# HashPower2.net
KiCad netlist of a schematic drawn in Altium Designer
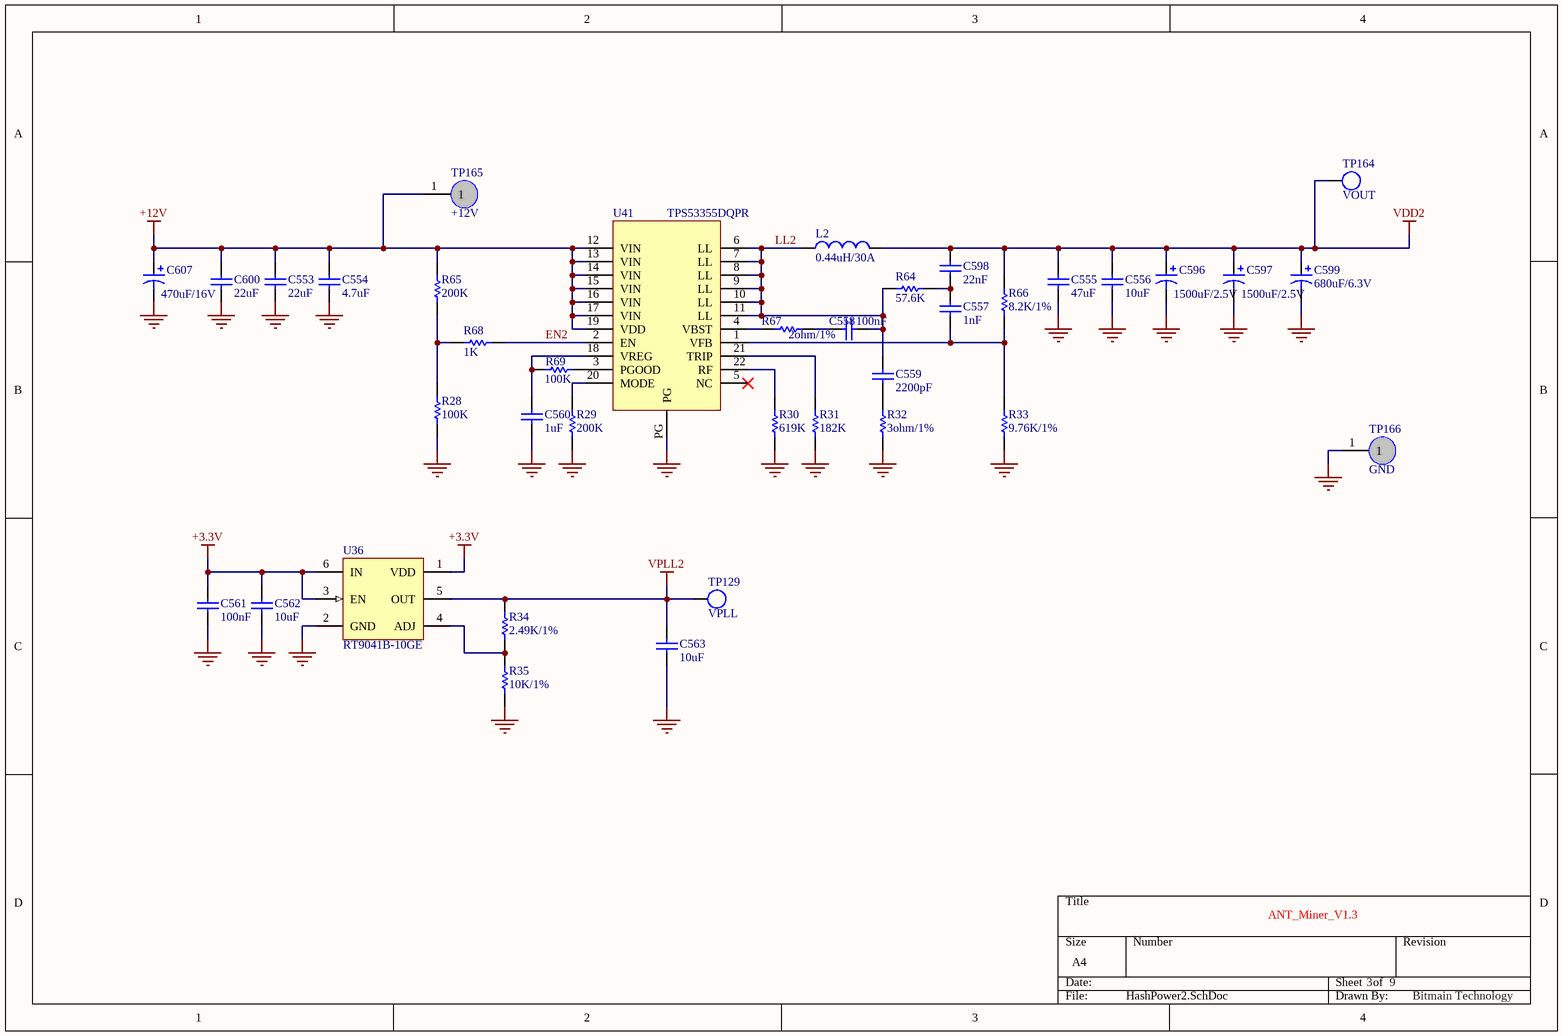
[diagram p0: HashPower2.SchDoc]

(export (version "E")
  (design (tool "Eeschema 10.0.6"))
  (components
    (comp (ref "C553")
      (value "22uF")
      (footprint "CC1210(3225)")
      (description "Capacitor")
      (libsource (lib "ANT_Miner_V1.3") (part "Cap"))
    )
    (comp (ref "C554")
      (value "4.7uF")
      (footprint "CC0805(2012)")
      (description "Capacitor")
      (libsource (lib "ANT_Miner_V1.3") (part "Cap"))
    )
    (comp (ref "C555")
      (value "47uF")
      (footprint "CAPC3225L")
      (description "Capacitor (Semiconductor SIM Model)")
      (fields (field (name "PUBLISHER") "Altium Limited"))
      (libsource (lib "Miscellaneous Devices") (part "Cap Semi"))
    )
    (comp (ref "C556")
      (value "10uF")
      (footprint "CAPC2012L")
      (description "Capacitor (Semiconductor SIM Model)")
      (fields (field (name "PUBLISHER") "Altium Limited"))
      (libsource (lib "Miscellaneous Devices") (part "Cap Semi"))
    )
    (comp (ref "C557")
      (value "1nF")
      (footprint "CC0603(1608)")
      (description "Capacitor")
      (libsource (lib "ANT_Miner_V1.3") (part "Cap"))
    )
    (comp (ref "C558")
      (value "100nF")
      (footprint "CC0603(1608)")
      (description "Capacitor")
      (libsource (lib "ANT_Miner_V1.3") (part "Cap"))
    )
    (comp (ref "C559")
      (value "2200pF")
      (footprint "CC0603(1608)")
      (description "Capacitor")
      (libsource (lib "ANT_Miner_V1.3") (part "Cap"))
    )
    (comp (ref "C560")
      (value "1uF")
      (footprint "CC0603(1608)")
      (description "Capacitor")
      (libsource (lib "ANT_Miner_V1.3") (part "Cap"))
    )
    (comp (ref "C561")
      (value "100nF")
      (footprint "CC0603(1608)")
      (description "Capacitor (Semiconductor SIM Model)")
      (fields (field (name "PUBLISHER") "Altium Limited"))
      (libsource (lib "CtrlUnit_10U_V1.0") (part "Cap Semi"))
    )
    (comp (ref "C562")
      (value "10uF")
      (footprint "CC0805(2012)")
      (description "Capacitor (Semiconductor SIM Model)")
      (fields (field (name "PUBLISHER") "Altium Limited"))
      (libsource (lib "CtrlUnit_10U_V1.0") (part "Cap Semi"))
    )
    (comp (ref "C563")
      (value "10uF")
      (footprint "CC0805(2012)")
      (description "Capacitor (Semiconductor SIM Model)")
      (fields (field (name "PUBLISHER") "Altium Limited"))
      (libsource (lib "CtrlUnit_10U_V1.0") (part "Cap Semi"))
    )
    (comp (ref "C596")
      (value "1500uF/2.5V")
      (footprint "F12")
      (description "Polarized Capacitor (SMD)")
      (fields (field (name "Comment") "1500uF/4V"))
      (libsource (lib "ANT_Miner_V1.3") (part "Cap Pol2"))
    )
    (comp (ref "C597")
      (value "1500uF/2.5V")
      (footprint "F12")
      (description "Polarized Capacitor (SMD)")
      (fields (field (name "Comment") "1500uF/4V"))
      (libsource (lib "ANT_Miner_V1.3") (part "Cap Pol2"))
    )
    (comp (ref "C598")
      (value "22nF")
      (footprint "CC0603(1608)")
      (description "Capacitor")
      (libsource (lib "ANT_Miner_V1.3") (part "Cap"))
    )
    (comp (ref "C599")
      (value "680uF/6.3V")
      (footprint "D")
      (description "Polarized Capacitor (Surface Mount)")
      (fields (field (name "PUBLISHER") "Altium Limited"))
      (libsource (lib "Miscellaneous Devices") (part "Cap Pol3"))
    )
    (comp (ref "C600")
      (value "22uF")
      (footprint "CC1210(3225)")
      (description "Capacitor")
      (libsource (lib "ANT_Miner_V1.3") (part "Cap"))
    )
    (comp (ref "C607")
      (value "470uF/16V")
      (footprint "E12")
      (description "Polarized Capacitor (SMD)")
      (libsource (lib "ANT_Miner_V1.3") (part "Cap Pol2"))
    )
    (comp (ref "L2")
      (value "0.44uH/30A")
      (footprint "IHLP5050")
      (description "Inductor")
      (fields (field (name "PUBLISHER") "Altium Limited"))
      (libsource (lib "Miscellaneous Devices") (part "Inductor"))
    )
    (comp (ref "R28")
      (value "100K")
      (footprint "RR0603(1608)")
      (description "Resistor")
      (libsource (lib "ANT_Miner_V1.3") (part "Res1"))
    )
    (comp (ref "R29")
      (value "200K")
      (footprint "RR0603(1608)")
      (description "Resistor")
      (libsource (lib "ANT_Miner_V1.3") (part "Res1"))
    )
    (comp (ref "R30")
      (value "619K")
      (footprint "RR0603(1608)")
      (description "Resistor")
      (libsource (lib "ANT_Miner_V1.3") (part "Res1"))
    )
    (comp (ref "R31")
      (value "182K")
      (footprint "RR0603(1608)")
      (description "Resistor")
      (libsource (lib "ANT_Miner_V1.3") (part "Res1"))
    )
    (comp (ref "R32")
      (value "3ohm/1%")
      (footprint "RR0603(1608)")
      (description "Resistor")
      (fields (field (name "Comment") "3"))
      (libsource (lib "ANT_Miner_V1.3") (part "Res1"))
    )
    (comp (ref "R33")
      (value "9.76K/1%")
      (footprint "RR0603(1608)")
      (description "Resistor")
      (libsource (lib "ANT_Miner_V1.3") (part "Res1"))
    )
    (comp (ref "R34")
      (value "2.49K/1%")
      (footprint "RR0603(1608)")
      (description "Resistor")
      (fields (field (name "PUBLISHER") "Altium Limited"))
      (libsource (lib "CtrlUnit_10U_V1.0") (part "Res1"))
    )
    (comp (ref "R35")
      (value "10K/1%")
      (footprint "RR0603(1608)")
      (description "Resistor")
      (fields (field (name "PUBLISHER") "Altium Limited"))
      (libsource (lib "CtrlUnit_10U_V1.0") (part "Res1"))
    )
    (comp (ref "R64")
      (value "57.6K")
      (footprint "RR0603(1608)")
      (description "Resistor")
      (libsource (lib "ANT_Miner_V1.3") (part "Res1"))
    )
    (comp (ref "R65")
      (value "200K")
      (footprint "RR0603(1608)")
      (description "Resistor")
      (libsource (lib "ANT_Miner_V1.3") (part "Res1"))
    )
    (comp (ref "R66")
      (value "8.2K/1%")
      (footprint "RR0603(1608)")
      (description "Resistor")
      (libsource (lib "ANT_Miner_V1.3") (part "Res1"))
    )
    (comp (ref "R67")
      (value "2ohm/1%")
      (footprint "RR0603(1608)")
      (description "Resistor")
      (fields (field (name "Comment") "2"))
      (libsource (lib "ANT_Miner_V1.3") (part "Res1"))
    )
    (comp (ref "R68")
      (value "1K")
      (footprint "RR0603(1608)")
      (description "Resistor")
      (libsource (lib "ANT_Miner_V1.3") (part "Res1"))
    )
    (comp (ref "R69")
      (value "100K")
      (footprint "RR0603(1608)")
      (description "Resistor")
      (libsource (lib "ANT_Miner_V1.3") (part "Res1"))
    )
    (comp (ref "TP129")
      (value "VPLL")
      (footprint "TP_SMD_1.0")
      (description "Test Point")
      (libsource (lib "BitMain_Miner_1") (part "TP"))
    )
    (comp (ref "TP164")
      (value "VOUT")
      (footprint "TP_SMD_1.0")
      (description "Test Point")
      (libsource (lib "BitMain_Miner_1") (part "TP"))
    )
    (comp (ref "TP165") (value "+12V") (footprint "TP") (libsource (lib "ANT_Miner_V1.3") (part "TP")))
    (comp (ref "TP166") (value "GND") (footprint "TP") (libsource (lib "ANT_Miner_V1.3") (part "TP")))
    (comp (ref "U36")
      (value "RT9041B-10GE")
      (footprint "SOT23-6_L")
      (libsource (lib "USB_Miner") (part "RT9041B-10GE"))
    )
    (comp (ref "U41")
      (value "TPS53355DQPR")
      (footprint "TPS53355")
      (libsource (lib "ANT_Miner_V1.3") (part "TPS53355"))
    )
  )
  (nets
    (net (code "1") (name "+3.3V") (class "Default")
      (node (ref "C561") (pin "2") (pinfunction "2_2") (pintype "passive"))
      (node (ref "C562") (pin "2") (pinfunction "2_2") (pintype "passive"))
      (node (ref "U36") (pin "1") (pinfunction "VDD_1") (pintype "power_in"))
      (node (ref "U36") (pin "3") (pinfunction "EN_3") (pintype "input"))
      (node (ref "U36") (pin "6") (pinfunction "IN_6") (pintype "power_in"))
    )
    (net (code "2") (name "+12V") (class "Default")
      (node (ref "C553") (pin "1") (pinfunction "1_1") (pintype "passive"))
      (node (ref "C554") (pin "1") (pinfunction "1_1") (pintype "passive"))
      (node (ref "C600") (pin "1") (pinfunction "1_1") (pintype "passive"))
      (node (ref "C607") (pin "1") (pinfunction "1_1") (pintype "passive"))
      (node (ref "R65") (pin "1") (pinfunction "1_1") (pintype "passive"))
      (node (ref "TP165") (pin "1") (pinfunction "1_1") (pintype "passive"))
      (node (ref "U41") (pin "12") (pinfunction "VIN_12") (pintype "passive"))
      (node (ref "U41") (pin "13") (pinfunction "VIN_13") (pintype "passive"))
      (node (ref "U41") (pin "14") (pinfunction "VIN_14") (pintype "passive"))
      (node (ref "U41") (pin "15") (pinfunction "VIN_15") (pintype "passive"))
      (node (ref "U41") (pin "16") (pinfunction "VIN_16") (pintype "passive"))
      (node (ref "U41") (pin "17") (pinfunction "VIN_17") (pintype "passive"))
      (node (ref "U41") (pin "19") (pinfunction "VDD_19") (pintype "passive"))
    )
    (net (code "3") (name "/EN2") (class "Default")
      (node (ref "R68") (pin "2") (pinfunction "2_2") (pintype "passive"))
      (node (ref "U41") (pin "2") (pinfunction "EN_2") (pintype "passive"))
    )
    (net (code "4") (name "/LL2") (class "Default")
      (node (ref "C558") (pin "2") (pinfunction "2_2") (pintype "passive"))
      (node (ref "C559") (pin "1") (pinfunction "1_1") (pintype "passive"))
      (node (ref "L2") (pin "1") (pinfunction "1_1") (pintype "passive"))
      (node (ref "R64") (pin "1") (pinfunction "1_1") (pintype "passive"))
      (node (ref "U41") (pin "10") (pinfunction "LL_10") (pintype "passive"))
      (node (ref "U41") (pin "11") (pinfunction "LL_11") (pintype "passive"))
      (node (ref "U41") (pin "6") (pinfunction "LL_6") (pintype "passive"))
      (node (ref "U41") (pin "7") (pinfunction "LL_7") (pintype "passive"))
      (node (ref "U41") (pin "8") (pinfunction "LL_8") (pintype "passive"))
      (node (ref "U41") (pin "9") (pinfunction "LL_9") (pintype "passive"))
    )
    (net (code "5") (name "GND") (class "Default")
      (node (ref "C553") (pin "2") (pinfunction "2_2") (pintype "passive"))
      (node (ref "C554") (pin "2") (pinfunction "2_2") (pintype "passive"))
      (node (ref "C555") (pin "1") (pinfunction "1_1") (pintype "passive"))
      (node (ref "C556") (pin "1") (pinfunction "1_1") (pintype "passive"))
      (node (ref "C560") (pin "2") (pinfunction "2_2") (pintype "passive"))
      (node (ref "C561") (pin "1") (pinfunction "1_1") (pintype "passive"))
      (node (ref "C562") (pin "1") (pinfunction "1_1") (pintype "passive"))
      (node (ref "C563") (pin "1") (pinfunction "1_1") (pintype "passive"))
      (node (ref "C596") (pin "2") (pinfunction "2_2") (pintype "passive"))
      (node (ref "C597") (pin "2") (pinfunction "2_2") (pintype "passive"))
      (node (ref "C599") (pin "2") (pinfunction "2_2") (pintype "passive"))
      (node (ref "C600") (pin "2") (pinfunction "2_2") (pintype "passive"))
      (node (ref "C607") (pin "2") (pinfunction "2_2") (pintype "passive"))
      (node (ref "R28") (pin "2") (pinfunction "2_2") (pintype "passive"))
      (node (ref "R29") (pin "2") (pinfunction "2_2") (pintype "passive"))
      (node (ref "R30") (pin "2") (pinfunction "2_2") (pintype "passive"))
      (node (ref "R31") (pin "2") (pinfunction "2_2") (pintype "passive"))
      (node (ref "R32") (pin "2") (pinfunction "2_2") (pintype "passive"))
      (node (ref "R33") (pin "2") (pinfunction "2_2") (pintype "passive"))
      (node (ref "R35") (pin "1") (pinfunction "1_1") (pintype "passive"))
      (node (ref "TP166") (pin "1") (pinfunction "1_1") (pintype "passive"))
      (node (ref "U36") (pin "2") (pinfunction "GND_2") (pintype "power_in"))
      (node (ref "U41") (pin "PG") (pinfunction "PG_PG") (pintype "passive"))
    )
    (net (code "6") (name "Net-(C557-Pad1)") (class "Default")
      (node (ref "C557") (pin "1") (pinfunction "1_1") (pintype "passive"))
      (node (ref "C598") (pin "2") (pinfunction "2_2") (pintype "passive"))
      (node (ref "R64") (pin "2") (pinfunction "2_2") (pintype "passive"))
    )
    (net (code "7") (name "Net-(C558-Pad1)") (class "Default")
      (node (ref "C558") (pin "1") (pinfunction "1_1") (pintype "passive"))
      (node (ref "R67") (pin "2") (pinfunction "2_2") (pintype "passive"))
    )
    (net (code "8") (name "Net-(C559-Pad2)") (class "Default")
      (node (ref "C559") (pin "2") (pinfunction "2_2") (pintype "passive"))
      (node (ref "R32") (pin "1") (pinfunction "1_1") (pintype "passive"))
    )
    (net (code "9") (name "Net-(R28-Pad1)") (class "Default")
      (node (ref "R28") (pin "1") (pinfunction "1_1") (pintype "passive"))
      (node (ref "R65") (pin "2") (pinfunction "2_2") (pintype "passive"))
      (node (ref "R68") (pin "1") (pinfunction "1_1") (pintype "passive"))
    )
    (net (code "10") (name "Net-(U36-ADJ)") (class "Default")
      (node (ref "R34") (pin "1") (pinfunction "1_1") (pintype "passive"))
      (node (ref "R35") (pin "2") (pinfunction "2_2") (pintype "passive"))
      (node (ref "U36") (pin "4") (pinfunction "ADJ_4") (pintype "passive"))
    )
    (net (code "11") (name "Net-(U41-MODE)") (class "Default")
      (node (ref "R29") (pin "1") (pinfunction "1_1") (pintype "passive"))
      (node (ref "U41") (pin "20") (pinfunction "MODE_20") (pintype "passive"))
    )
    (net (code "12") (name "Net-(U41-PGOOD)") (class "Default")
      (node (ref "R69") (pin "2") (pinfunction "2_2") (pintype "passive"))
      (node (ref "U41") (pin "3") (pinfunction "PGOOD_3") (pintype "passive"))
    )
    (net (code "13") (name "Net-(U41-RF)") (class "Default")
      (node (ref "R30") (pin "1") (pinfunction "1_1") (pintype "passive"))
      (node (ref "U41") (pin "22") (pinfunction "RF_22") (pintype "passive"))
    )
    (net (code "14") (name "Net-(U41-TRIP)") (class "Default")
      (node (ref "R31") (pin "1") (pinfunction "1_1") (pintype "passive"))
      (node (ref "U41") (pin "21") (pinfunction "TRIP_21") (pintype "passive"))
    )
    (net (code "15") (name "Net-(U41-VBST)") (class "Default")
      (node (ref "R67") (pin "1") (pinfunction "1_1") (pintype "passive"))
      (node (ref "U41") (pin "4") (pinfunction "VBST_4") (pintype "passive"))
    )
    (net (code "16") (name "Net-(U41-VFB)") (class "Default")
      (node (ref "C557") (pin "2") (pinfunction "2_2") (pintype "passive"))
      (node (ref "R33") (pin "1") (pinfunction "1_1") (pintype "passive"))
      (node (ref "R66") (pin "2") (pinfunction "2_2") (pintype "passive"))
      (node (ref "U41") (pin "1") (pinfunction "VFB_1") (pintype "passive"))
    )
    (net (code "17") (name "Net-(U41-VREG)") (class "Default")
      (node (ref "C560") (pin "1") (pinfunction "1_1") (pintype "passive"))
      (node (ref "R69") (pin "1") (pinfunction "1_1") (pintype "passive"))
      (node (ref "U41") (pin "18") (pinfunction "VREG_18") (pintype "passive"))
    )
    (net (code "18") (name "VDD2") (class "Default")
      (node (ref "C555") (pin "2") (pinfunction "2_2") (pintype "passive"))
      (node (ref "C556") (pin "2") (pinfunction "2_2") (pintype "passive"))
      (node (ref "C596") (pin "1") (pinfunction "1_1") (pintype "passive"))
      (node (ref "C597") (pin "1") (pinfunction "1_1") (pintype "passive"))
      (node (ref "C598") (pin "1") (pinfunction "1_1") (pintype "passive"))
      (node (ref "C599") (pin "1") (pinfunction "1_1") (pintype "passive"))
      (node (ref "L2") (pin "2") (pinfunction "2_2") (pintype "passive"))
      (node (ref "R66") (pin "1") (pinfunction "1_1") (pintype "passive"))
      (node (ref "TP164") (pin "1") (pinfunction "1_1") (pintype "passive"))
    )
    (net (code "19") (name "VPLL2") (class "Default")
      (node (ref "C563") (pin "2") (pinfunction "2_2") (pintype "passive"))
      (node (ref "R34") (pin "2") (pinfunction "2_2") (pintype "passive"))
      (node (ref "TP129") (pin "1") (pinfunction "1_1") (pintype "passive"))
      (node (ref "U36") (pin "5") (pinfunction "OUT_5") (pintype "power_in"))
    )
    (net (code "20") (name "unconnected-(U41-NC-Pad5)") (class "Default")
      (node (ref "U41") (pin "5") (pinfunction "NC_5") (pintype "passive+no_connect"))
    )
  )
)
